# single_v4.net
KiCad netlist of a schematic drawn in EAGLE
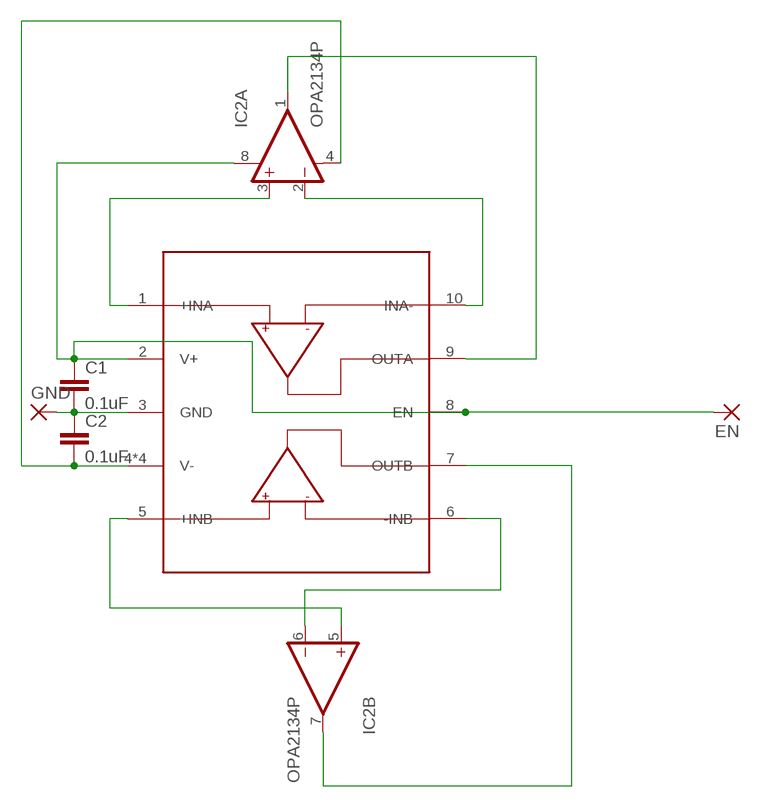
[diagram p0: schematic, sheet 1]

(export (version "E")
  (design (tool "Eeschema 10.0.6"))
  (components
    (comp (ref "C1")
      (value "0.1uF")
      (footprint "eagle-import:C0805")
      (libsource (lib "eagle-import") (part "C-EUC0805"))
    )
    (comp (ref "C2")
      (value "0.1uF")
      (footprint "eagle-import:C0805")
      (libsource (lib "eagle-import") (part "C-EUC0805"))
    )
    (comp (ref "EN")
      (value "1,6/0,8")
      (footprint "eagle-import:1,6_0,8")
      (libsource (lib "eagle-import") (part "1,6/0,8"))
    )
    (comp (ref "GND")
      (value "1,6/0,8")
      (footprint "eagle-import:1,6_0,8")
      (libsource (lib "eagle-import") (part "1,6/0,8"))
    )
    (comp (ref "IC1")
      (value "OPA1622")
      (footprint "eagle-import:S-PDSO-N10")
      (libsource (lib "eagle-import") (part "OPA1622"))
    )
    (comp (ref "IC2")
      (value "OPA2134P")
      (footprint "eagle-import:DIL08")
      (fields (field (name "MF") "TEXAS INSTRUMENTS") (field (name "MPN") "OPA2134PA"))
      (libsource (lib "eagle-import") (part "OPA2134P"))
    )
  )
  (nets
    (net (code "1") (name "Net-(EN-P)") (class "Default")
      (node (ref "C1") (pin "1") (pinfunction "1_1") (pintype "passive"))
      (node (ref "EN") (pin "1") (pinfunction "P_1") (pintype "passive"))
      (node (ref "IC1") (pin "2") (pinfunction "V+_2") (pintype "power_in"))
      (node (ref "IC1") (pin "8") (pinfunction "EN_8") (pintype "power_in"))
      (node (ref "IC2") (pin "8") (pinfunction "V+_8") (pintype "power_in"))
    )
    (net (code "2") (name "Net-(GND-P)") (class "Default")
      (node (ref "C1") (pin "2") (pinfunction "2_2") (pintype "passive"))
      (node (ref "C2") (pin "1") (pinfunction "1_1") (pintype "passive"))
      (node (ref "GND") (pin "1") (pinfunction "P_1") (pintype "passive"))
      (node (ref "IC1") (pin "3") (pinfunction "GND_3") (pintype "power_in"))
    )
    (net (code "3") (name "Net-(IC1-+INA)") (class "Default")
      (node (ref "IC1") (pin "1") (pinfunction "+INA_1") (pintype "input"))
      (node (ref "IC2") (pin "3") (pinfunction "+IN_3") (pintype "input"))
    )
    (net (code "4") (name "Net-(IC1-+INB)") (class "Default")
      (node (ref "IC1") (pin "5") (pinfunction "+INB_5") (pintype "input"))
      (node (ref "IC2") (pin "5") (pinfunction "+IN_5") (pintype "input"))
    )
    (net (code "5") (name "Net-(IC1--INB)") (class "Default")
      (node (ref "IC1") (pin "6") (pinfunction "-INB_6") (pintype "input"))
      (node (ref "IC2") (pin "6") (pinfunction "-IN_6") (pintype "input"))
    )
    (net (code "6") (name "Net-(IC1-INA-)") (class "Default")
      (node (ref "IC1") (pin "10") (pinfunction "INA-_10") (pintype "input"))
      (node (ref "IC2") (pin "2") (pinfunction "-IN_2") (pintype "input"))
    )
    (net (code "7") (name "Net-(IC1-OUTA)") (class "Default")
      (node (ref "IC1") (pin "9") (pinfunction "OUTA_9") (pintype "output"))
      (node (ref "IC2") (pin "1") (pinfunction "OUT_1") (pintype "output"))
    )
    (net (code "8") (name "Net-(IC1-OUTB)") (class "Default")
      (node (ref "IC1") (pin "7") (pinfunction "OUTB_7") (pintype "output"))
      (node (ref "IC2") (pin "7") (pinfunction "OUT_7") (pintype "output"))
    )
    (net (code "9") (name "Net-(IC2A-V-)") (class "Default")
      (node (ref "C2") (pin "2") (pinfunction "2_2") (pintype "passive"))
      (node (ref "IC1") (pin "4") (pinfunction "V-_4") (pintype "power_in"))
      (node (ref "IC1") (pin "PP") (pinfunction "V-_PP") (pintype "power_in"))
      (node (ref "IC1") (pin "PP@1") (pinfunction "V-_PP@1") (pintype "power_in"))
      (node (ref "IC1") (pin "PP@2") (pinfunction "V-_PP@2") (pintype "power_in"))
      (node (ref "IC2") (pin "4") (pinfunction "V-_4") (pintype "power_in"))
    )
  )
)
